# PennyMan_Ard_R3_Shield_v4a.net
KiCad netlist of a schematic drawn in EAGLE
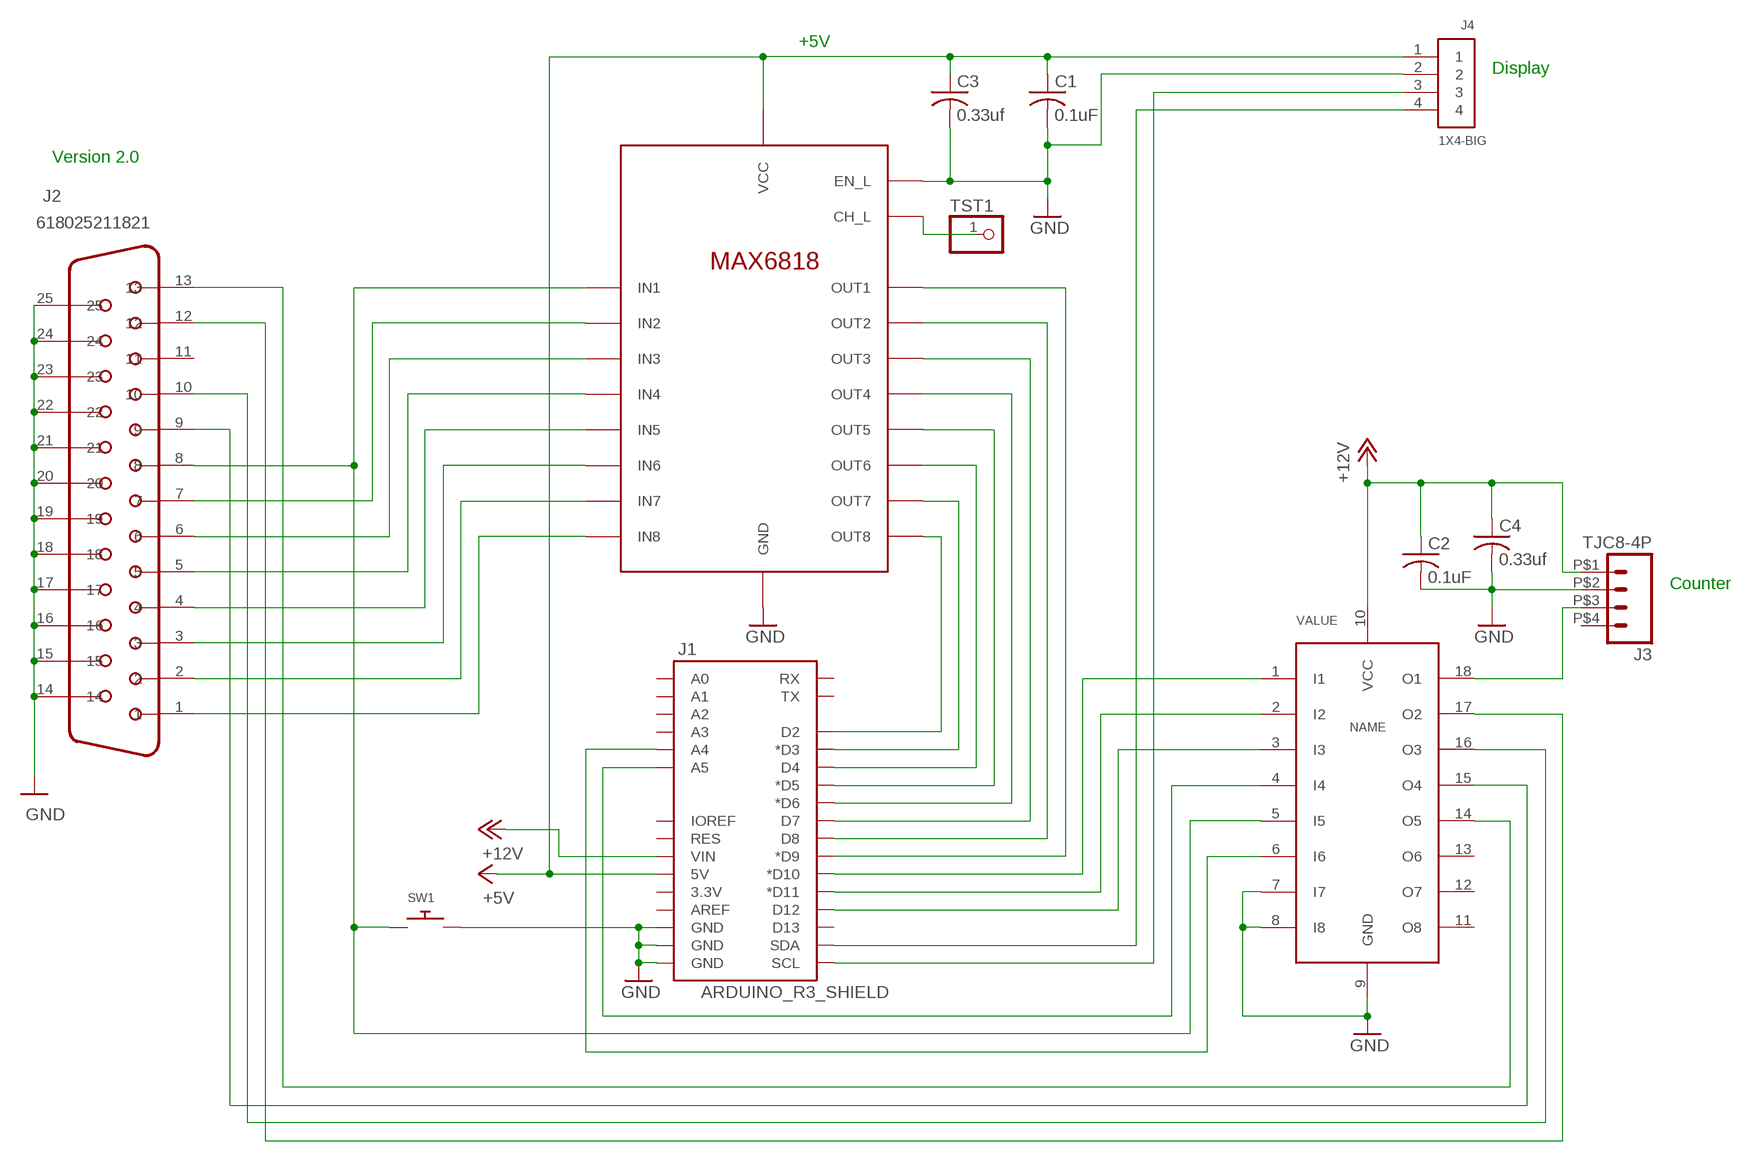
[diagram p0: schematic, sheet 1]

(export (version "E")
  (design (tool "Eeschema 10.0.6"))
  (components
    (comp (ref "C1")
      (value "0.1uF")
      (footprint "eagle-import:C0805")
      (libsource (lib "eagle-import") (part "C-USC0805"))
    )
    (comp (ref "C2")
      (value "0.1uF")
      (footprint "eagle-import:C0805")
      (libsource (lib "eagle-import") (part "C-USC0805"))
    )
    (comp (ref "C3")
      (value "0.33uf")
      (footprint "eagle-import:C1206")
      (libsource (lib "eagle-import") (part "C-USC1206"))
    )
    (comp (ref "C4")
      (value "0.33uf")
      (footprint "eagle-import:C1206")
      (libsource (lib "eagle-import") (part "C-USC1206"))
    )
    (comp (ref "J1")
      (value "ARDUINO_R3_SHIELD")
      (footprint "eagle-import:UNO_R3_SHIELD")
      (libsource (lib "eagle-import") (part "ARDUINO_R3_SHIELD"))
    )
    (comp (ref "J2")
      (value "618025211821")
      (footprint "eagle-import:618025211821")
      (libsource (lib "eagle-import") (part "618025211821"))
    )
    (comp (ref "J3")
      (value "TJC8-4P")
      (footprint "eagle-import:TJC8-4P")
      (libsource (lib "eagle-import") (part "TJC8-4P"))
    )
    (comp (ref "J4")
      (value "1X4-BIG")
      (footprint "eagle-import:1X04-BIG")
      (libsource (lib "eagle-import") (part "1X4-BIG"))
    )
    (comp (ref "SW1")
      (value "SWITCH_PUSHBUTTONEVQ-PE")
      (footprint "eagle-import:TACT_PANA-EVQ")
      (libsource (lib "eagle-import") (part "SWITCH_PUSHBUTTONEVQ-PE"))
    )
    (comp (ref "TST1")
      (value "PINHD-1X1")
      (footprint "eagle-import:1X01")
      (libsource (lib "eagle-import") (part "PINHD-1X1"))
    )
    (comp (ref "U1")
      (value "MAX6818")
      (footprint "eagle-import:SSOP20")
      (libsource (lib "eagle-import") (part "MAX6818"))
    )
    (comp (ref "U2")
      (value "TD62783AG")
      (footprint "eagle-import:SOP18")
      (libsource (lib "eagle-import") (part "TD62783AG"))
    )
  )
  (nets
    (net (code "1") (name "+5V") (class "Default")
      (node (ref "C1") (pin "1") (pinfunction "1_1") (pintype "passive"))
      (node (ref "C3") (pin "1") (pinfunction "1_1") (pintype "passive"))
      (node (ref "J1") (pin "5V") (pinfunction "5V_5V") (pintype "bidirectional"))
      (node (ref "J4") (pin "1") (pinfunction "1_1") (pintype "bidirectional"))
      (node (ref "U1") (pin "VCC") (pinfunction "VCC_VCC") (pintype "bidirectional"))
    )
    (net (code "2") (name "+12V") (class "Default")
      (node (ref "C2") (pin "1") (pinfunction "1_1") (pintype "passive"))
      (node (ref "C4") (pin "1") (pinfunction "1_1") (pintype "passive"))
      (node (ref "J1") (pin "VIN") (pinfunction "VIN_VIN") (pintype "bidirectional"))
      (node (ref "J3") (pin "P$1") (pinfunction "1_P$1") (pintype "passive"))
      (node (ref "U2") (pin "10") (pinfunction "VCC_10") (pintype "bidirectional"))
    )
    (net (code "3") (name "GND") (class "Default")
      (node (ref "C1") (pin "2") (pinfunction "2_2") (pintype "passive"))
      (node (ref "C2") (pin "2") (pinfunction "2_2") (pintype "passive"))
      (node (ref "C3") (pin "2") (pinfunction "2_2") (pintype "passive"))
      (node (ref "C4") (pin "2") (pinfunction "2_2") (pintype "passive"))
      (node (ref "J1") (pin "GND@0") (pinfunction "GND_GND@0") (pintype "bidirectional"))
      (node (ref "J1") (pin "GND@1") (pinfunction "GND_GND@1") (pintype "bidirectional"))
      (node (ref "J1") (pin "GND@2") (pinfunction "GND_GND@2") (pintype "bidirectional"))
      (node (ref "J2") (pin "14") (pinfunction "14_14") (pintype "bidirectional"))
      (node (ref "J2") (pin "15") (pinfunction "15_15") (pintype "bidirectional"))
      (node (ref "J2") (pin "16") (pinfunction "16_16") (pintype "bidirectional"))
      (node (ref "J2") (pin "17") (pinfunction "17_17") (pintype "bidirectional"))
      (node (ref "J2") (pin "18") (pinfunction "18_18") (pintype "bidirectional"))
      (node (ref "J2") (pin "19") (pinfunction "19_19") (pintype "bidirectional"))
      (node (ref "J2") (pin "20") (pinfunction "20_20") (pintype "bidirectional"))
      (node (ref "J2") (pin "21") (pinfunction "21_21") (pintype "bidirectional"))
      (node (ref "J2") (pin "22") (pinfunction "22_22") (pintype "bidirectional"))
      (node (ref "J2") (pin "23") (pinfunction "23_23") (pintype "bidirectional"))
      (node (ref "J2") (pin "24") (pinfunction "24_24") (pintype "bidirectional"))
      (node (ref "J2") (pin "25") (pinfunction "25_25") (pintype "bidirectional"))
      (node (ref "J3") (pin "P$2") (pinfunction "2_P$2") (pintype "passive"))
      (node (ref "J4") (pin "2") (pinfunction "2_2") (pintype "bidirectional"))
      (node (ref "SW1") (pin "P$2") (pinfunction "P$2_P$2") (pintype "passive"))
      (node (ref "U1") (pin "EN_L") (pinfunction "EN_L_EN_L") (pintype "bidirectional"))
      (node (ref "U1") (pin "GND") (pinfunction "GND_GND") (pintype "bidirectional"))
      (node (ref "U2") (pin "7") (pinfunction "I7_7") (pintype "bidirectional"))
      (node (ref "U2") (pin "8") (pinfunction "I8_8") (pintype "bidirectional"))
      (node (ref "U2") (pin "9") (pinfunction "GND_9") (pintype "bidirectional"))
    )
    (net (code "4") (name "Net-(J1-*D3)") (class "Default")
      (node (ref "J1") (pin "D3") (pinfunction "*D3_D3") (pintype "bidirectional"))
      (node (ref "U1") (pin "OUT7") (pinfunction "OUT7_OUT7") (pintype "bidirectional"))
    )
    (net (code "5") (name "Net-(J1-*D5)") (class "Default")
      (node (ref "J1") (pin "D5") (pinfunction "*D5_D5") (pintype "bidirectional"))
      (node (ref "U1") (pin "OUT5") (pinfunction "OUT5_OUT5") (pintype "bidirectional"))
    )
    (net (code "6") (name "Net-(J1-*D6)") (class "Default")
      (node (ref "J1") (pin "D6") (pinfunction "*D6_D6") (pintype "bidirectional"))
      (node (ref "U1") (pin "OUT4") (pinfunction "OUT4_OUT4") (pintype "bidirectional"))
    )
    (net (code "7") (name "Net-(J1-*D9)") (class "Default")
      (node (ref "J1") (pin "D9") (pinfunction "*D9_D9") (pintype "bidirectional"))
      (node (ref "U1") (pin "OUT1") (pinfunction "OUT1_OUT1") (pintype "bidirectional"))
    )
    (net (code "8") (name "Net-(J1-*D10)") (class "Default")
      (node (ref "J1") (pin "D10") (pinfunction "*D10_D10") (pintype "bidirectional"))
      (node (ref "U2") (pin "1") (pinfunction "I1_1") (pintype "bidirectional"))
    )
    (net (code "9") (name "Net-(J1-*D11)") (class "Default")
      (node (ref "J1") (pin "D11") (pinfunction "*D11_D11") (pintype "bidirectional"))
      (node (ref "U2") (pin "2") (pinfunction "I2_2") (pintype "bidirectional"))
    )
    (net (code "10") (name "Net-(J1-PadD2)") (class "Default")
      (node (ref "J1") (pin "D2") (pinfunction "D2_D2") (pintype "bidirectional"))
      (node (ref "U1") (pin "OUT8") (pinfunction "OUT8_OUT8") (pintype "bidirectional"))
    )
    (net (code "11") (name "Net-(J1-PadD4)") (class "Default")
      (node (ref "J1") (pin "D4") (pinfunction "D4_D4") (pintype "bidirectional"))
      (node (ref "U1") (pin "OUT6") (pinfunction "OUT6_OUT6") (pintype "bidirectional"))
    )
    (net (code "12") (name "Net-(J1-PadD7)") (class "Default")
      (node (ref "J1") (pin "D7") (pinfunction "D7_D7") (pintype "bidirectional"))
      (node (ref "U1") (pin "OUT3") (pinfunction "OUT3_OUT3") (pintype "bidirectional"))
    )
    (net (code "13") (name "Net-(J1-PadD8)") (class "Default")
      (node (ref "J1") (pin "D8") (pinfunction "D8_D8") (pintype "bidirectional"))
      (node (ref "U1") (pin "OUT2") (pinfunction "OUT2_OUT2") (pintype "bidirectional"))
    )
    (net (code "14") (name "Net-(J1-PadSCL)") (class "Default")
      (node (ref "J1") (pin "SCL") (pinfunction "SCL_SCL") (pintype "bidirectional"))
      (node (ref "J4") (pin "3") (pinfunction "3_3") (pintype "bidirectional"))
    )
    (net (code "15") (name "Net-(J1-PadSDA)") (class "Default")
      (node (ref "J1") (pin "SDA") (pinfunction "SDA_SDA") (pintype "bidirectional"))
      (node (ref "J4") (pin "4") (pinfunction "4_4") (pintype "bidirectional"))
    )
    (net (code "16") (name "Net-(J2-Pad1)") (class "Default")
      (node (ref "J2") (pin "1") (pinfunction "1_1") (pintype "bidirectional"))
      (node (ref "U1") (pin "IN8") (pinfunction "IN8_IN8") (pintype "bidirectional"))
    )
    (net (code "17") (name "Net-(J2-Pad2)") (class "Default")
      (node (ref "J2") (pin "2") (pinfunction "2_2") (pintype "bidirectional"))
      (node (ref "U1") (pin "IN7") (pinfunction "IN7_IN7") (pintype "bidirectional"))
    )
    (net (code "18") (name "Net-(J2-Pad3)") (class "Default")
      (node (ref "J2") (pin "3") (pinfunction "3_3") (pintype "bidirectional"))
      (node (ref "U1") (pin "IN6") (pinfunction "IN6_IN6") (pintype "bidirectional"))
    )
    (net (code "19") (name "Net-(J2-Pad4)") (class "Default")
      (node (ref "J2") (pin "4") (pinfunction "4_4") (pintype "bidirectional"))
      (node (ref "U1") (pin "IN5") (pinfunction "IN5_IN5") (pintype "bidirectional"))
    )
    (net (code "20") (name "Net-(J2-Pad5)") (class "Default")
      (node (ref "J2") (pin "5") (pinfunction "5_5") (pintype "bidirectional"))
      (node (ref "U1") (pin "IN4") (pinfunction "IN4_IN4") (pintype "bidirectional"))
    )
    (net (code "21") (name "Net-(J2-Pad6)") (class "Default")
      (node (ref "J2") (pin "6") (pinfunction "6_6") (pintype "bidirectional"))
      (node (ref "U1") (pin "IN3") (pinfunction "IN3_IN3") (pintype "bidirectional"))
    )
    (net (code "22") (name "Net-(J2-Pad7)") (class "Default")
      (node (ref "J2") (pin "7") (pinfunction "7_7") (pintype "bidirectional"))
      (node (ref "U1") (pin "IN2") (pinfunction "IN2_IN2") (pintype "bidirectional"))
    )
    (net (code "23") (name "Net-(J3-3)") (class "Default")
      (node (ref "J3") (pin "P$3") (pinfunction "3_P$3") (pintype "passive"))
      (node (ref "U2") (pin "18") (pinfunction "O1_18") (pintype "bidirectional"))
    )
    (net (code "24") (name "Net-(TST1-Pad1)") (class "Default")
      (node (ref "TST1") (pin "1") (pinfunction "1_1") (pintype "passive"))
      (node (ref "U1") (pin "CH_L") (pinfunction "CH_L_CH_L") (pintype "bidirectional"))
    )
    (net (code "25") (name "Net-(U2-I3)") (class "Default")
      (node (ref "J1") (pin "D12") (pinfunction "D12_D12") (pintype "bidirectional"))
      (node (ref "U2") (pin "3") (pinfunction "I3_3") (pintype "bidirectional"))
    )
    (net (code "26") (name "Net-(U2-I4)") (class "Default")
      (node (ref "J1") (pin "A5") (pinfunction "A5_A5") (pintype "bidirectional"))
      (node (ref "U2") (pin "4") (pinfunction "I4_4") (pintype "bidirectional"))
    )
    (net (code "27") (name "Net-(U2-I5)") (class "Default")
      (node (ref "J2") (pin "8") (pinfunction "8_8") (pintype "bidirectional"))
      (node (ref "SW1") (pin "P$1") (pinfunction "P$1_P$1") (pintype "passive"))
      (node (ref "U1") (pin "IN1") (pinfunction "IN1_IN1") (pintype "bidirectional"))
      (node (ref "U2") (pin "5") (pinfunction "I5_5") (pintype "bidirectional"))
    )
    (net (code "28") (name "Net-(U2-I6)") (class "Default")
      (node (ref "J1") (pin "A4") (pinfunction "A4_A4") (pintype "bidirectional"))
      (node (ref "U2") (pin "6") (pinfunction "I6_6") (pintype "bidirectional"))
    )
    (net (code "29") (name "Net-(U2-O2)") (class "Default")
      (node (ref "J2") (pin "12") (pinfunction "12_12") (pintype "bidirectional"))
      (node (ref "U2") (pin "17") (pinfunction "O2_17") (pintype "bidirectional"))
    )
    (net (code "30") (name "Net-(U2-O3)") (class "Default")
      (node (ref "J2") (pin "10") (pinfunction "10_10") (pintype "bidirectional"))
      (node (ref "U2") (pin "16") (pinfunction "O3_16") (pintype "bidirectional"))
    )
    (net (code "31") (name "Net-(U2-O4)") (class "Default")
      (node (ref "J2") (pin "9") (pinfunction "9_9") (pintype "bidirectional"))
      (node (ref "U2") (pin "15") (pinfunction "O4_15") (pintype "bidirectional"))
    )
    (net (code "32") (name "Net-(U2-O5)") (class "Default")
      (node (ref "J2") (pin "13") (pinfunction "13_13") (pintype "bidirectional"))
      (node (ref "U2") (pin "14") (pinfunction "O5_14") (pintype "bidirectional"))
    )
    (net (code "33") (name "unconnected-(J1-Pad3.3V)") (class "Default")
      (node (ref "J1") (pin "3.3V") (pinfunction "3.3V_3.3V") (pintype "bidirectional"))
    )
    (net (code "34") (name "unconnected-(J1-PadA0)") (class "Default")
      (node (ref "J1") (pin "A0") (pinfunction "A0_A0") (pintype "bidirectional"))
    )
    (net (code "35") (name "unconnected-(J1-PadA1)") (class "Default")
      (node (ref "J1") (pin "A1") (pinfunction "A1_A1") (pintype "bidirectional"))
    )
    (net (code "36") (name "unconnected-(J1-PadA2)") (class "Default")
      (node (ref "J1") (pin "A2") (pinfunction "A2_A2") (pintype "bidirectional"))
    )
    (net (code "37") (name "unconnected-(J1-PadA3)") (class "Default")
      (node (ref "J1") (pin "A3") (pinfunction "A3_A3") (pintype "bidirectional"))
    )
    (net (code "38") (name "unconnected-(J1-PadAREF)") (class "Default")
      (node (ref "J1") (pin "AREF") (pinfunction "AREF_AREF") (pintype "bidirectional"))
    )
    (net (code "39") (name "unconnected-(J1-PadD13)") (class "Default")
      (node (ref "J1") (pin "D13") (pinfunction "D13_D13") (pintype "bidirectional"))
    )
    (net (code "40") (name "unconnected-(J1-PadIOREF)") (class "Default")
      (node (ref "J1") (pin "IOREF") (pinfunction "IOREF_IOREF") (pintype "bidirectional"))
    )
    (net (code "41") (name "unconnected-(J1-PadRES)") (class "Default")
      (node (ref "J1") (pin "RES") (pinfunction "RES_RES") (pintype "bidirectional"))
    )
    (net (code "42") (name "unconnected-(J1-PadRX)") (class "Default")
      (node (ref "J1") (pin "RX") (pinfunction "RX_RX") (pintype "bidirectional"))
    )
    (net (code "43") (name "unconnected-(J1-PadTX)") (class "Default")
      (node (ref "J1") (pin "TX") (pinfunction "TX_TX") (pintype "bidirectional"))
    )
    (net (code "44") (name "unconnected-(J2-Pad11)") (class "Default")
      (node (ref "J2") (pin "11") (pinfunction "11_11") (pintype "bidirectional"))
    )
    (net (code "45") (name "unconnected-(J3-4-PadP$4)") (class "Default")
      (node (ref "J3") (pin "P$4") (pinfunction "4_P$4") (pintype "passive"))
    )
    (net (code "46") (name "unconnected-(U2-O6-Pad13)") (class "Default")
      (node (ref "U2") (pin "13") (pinfunction "O6_13") (pintype "bidirectional"))
    )
    (net (code "47") (name "unconnected-(U2-O7-Pad12)") (class "Default")
      (node (ref "U2") (pin "12") (pinfunction "O7_12") (pintype "bidirectional"))
    )
    (net (code "48") (name "unconnected-(U2-O8-Pad11)") (class "Default")
      (node (ref "U2") (pin "11") (pinfunction "O8_11") (pintype "bidirectional"))
    )
  )
)
